# USBC_A.net
KiCad netlist of a schematic drawn in Altium Designer
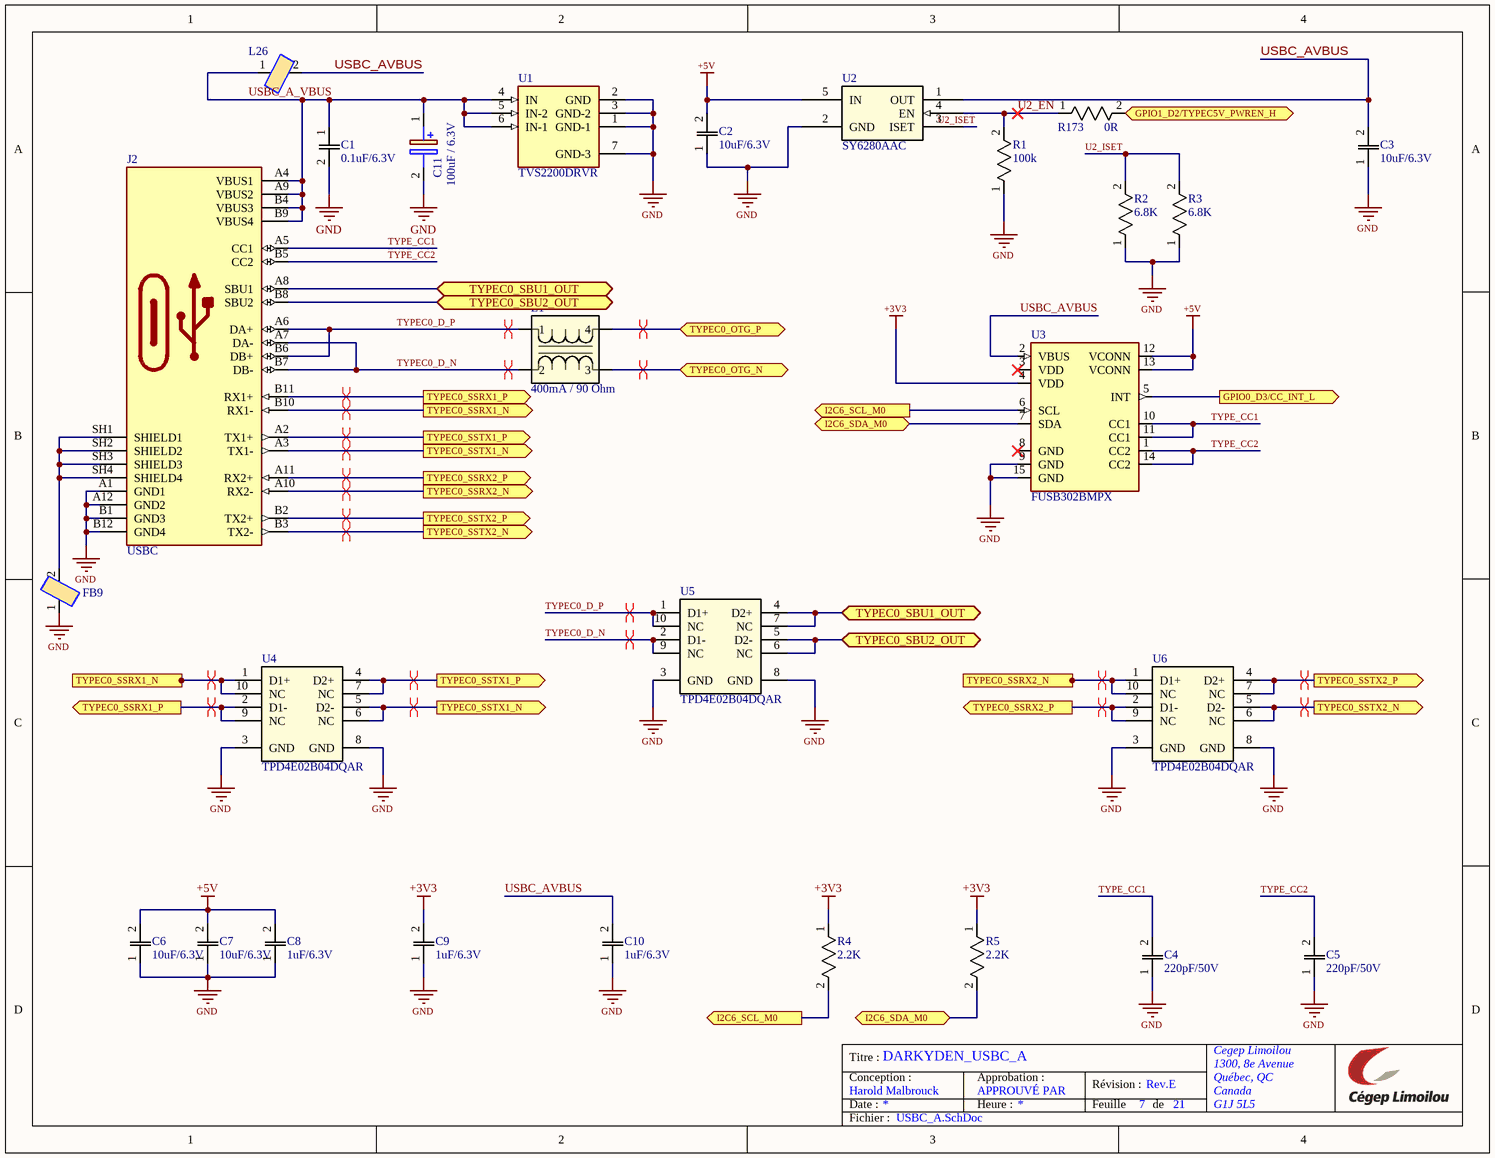
[diagram p0: USBC_A.SchDoc]

(export (version "E")
  (design (tool "Eeschema 10.0.6"))
  (components
    (comp (ref "C1")
      (value "0.1uF/6.3V")
      (footprint "C0805")
      (description "0.1uF 6.3V X7R 10% Pad SMD 0805 125C T/R")
      (fields
        (field (name "MOUSER PART NUMBER") "80-C0805C104K9R")
        (field (name "ARROW PART NUMBER") "C0805C104K9RACTU")
      )
      (libsource (lib "DARKYDEN") (part "C0805C104K9RACTU"))
    )
    (comp (ref "C2")
      (value "10uF/6.3V")
      (footprint "C0805")
      (fields
        (field (name "MOUSER PART NUMBER") "80-C0805C106K9R")
        (field (name "ARROW PART NUMBER") "C0805C106K9RACTU")
        (field (name "MANUFACTURER") "KEMET")
      )
      (libsource (lib "DARKYDEN") (part "C0805C106K9RACTU"))
    )
    (comp (ref "C3")
      (value "10uF/6.3V")
      (footprint "C0805")
      (fields
        (field (name "MOUSER PART NUMBER") "80-C0805C106K9R")
        (field (name "ARROW PART NUMBER") "C0805C106K9RACTU")
        (field (name "MANUFACTURER") "KEMET")
      )
      (libsource (lib "DARKYDEN") (part "C0805C106K9RACTU"))
    )
    (comp (ref "C4")
      (value "220pF/50V")
      (footprint "C0805")
      (description "Cap Ceramic 220pF 50V X7R 20% Pad SMD 0805 125C T/R")
      (fields
        (field (name "MANUFACTURER") "KEMET")
        (field (name "MANUFACTURER PART NUMBER") "C0805C221M5RACTU")
      )
      (libsource (lib "DARKYDEN") (part "C0805C221M5RACTU"))
    )
    (comp (ref "C5")
      (value "220pF/50V")
      (footprint "C0805")
      (description "Cap Ceramic 220pF 50V X7R 20% Pad SMD 0805 125C T/R")
      (fields
        (field (name "MANUFACTURER") "KEMET")
        (field (name "MANUFACTURER PART NUMBER") "C0805C221M5RACTU")
      )
      (libsource (lib "DARKYDEN") (part "C0805C221M5RACTU"))
    )
    (comp (ref "C6")
      (value "10uF/6.3V")
      (footprint "C0805")
      (fields
        (field (name "MOUSER PART NUMBER") "80-C0805C106K9R")
        (field (name "ARROW PART NUMBER") "C0805C106K9RACTU")
        (field (name "MANUFACTURER") "KEMET")
      )
      (libsource (lib "DARKYDEN") (part "C0805C106K9RACTU"))
    )
    (comp (ref "C7")
      (value "10uF/6.3V")
      (footprint "C0805")
      (fields
        (field (name "MOUSER PART NUMBER") "80-C0805C106K9R")
        (field (name "ARROW PART NUMBER") "C0805C106K9RACTU")
        (field (name "MANUFACTURER") "KEMET")
      )
      (libsource (lib "DARKYDEN") (part "C0805C106K9RACTU"))
    )
    (comp (ref "C8")
      (value "1uF/6.3V")
      (footprint "C0805")
      (description "1 uF, 6.3 V, ± 10%, X7R, 0805 [2012 Metric] Multilayer Ceramic Capacitor,")
      (fields
        (field (name "MOUSER PART NUMBER") "80-C0805C105K9R")
        (field (name "ARROW PART NUMBER") "C0805C105K9RACTU")
      )
      (libsource (lib "DARKYDEN") (part "C0805C105K9RACTU"))
    )
    (comp (ref "C9")
      (value "1uF/6.3V")
      (footprint "C0805")
      (description "1 uF, 6.3 V, ± 10%, X7R, 0805 [2012 Metric] Multilayer Ceramic Capacitor,")
      (fields
        (field (name "MOUSER PART NUMBER") "80-C0805C105K9R")
        (field (name "ARROW PART NUMBER") "C0805C105K9RACTU")
      )
      (libsource (lib "DARKYDEN") (part "C0805C105K9RACTU"))
    )
    (comp (ref "C10")
      (value "1uF/6.3V")
      (footprint "C0805")
      (description "1 uF, 6.3 V, ± 10%, X7R, 0805 [2012 Metric] Multilayer Ceramic Capacitor,")
      (fields
        (field (name "MOUSER PART NUMBER") "80-C0805C105K9R")
        (field (name "ARROW PART NUMBER") "C0805C105K9RACTU")
      )
      (libsource (lib "DARKYDEN") (part "C0805C105K9RACTU"))
    )
    (comp (ref "C11")
      (value "100uF / 6.3V")
      (footprint "SamacSys:EEE0GA101SR")
      (description "100uF 6.3V 20% Cap Aluminum Lytic  SMD 0.36 Ohm 240mA 2000h 105C Automotive T/R")
      (fields
        (field (name "MOUSER PART NUMBER") "667-EEE-FPJ101UAR")
        (field (name "ARROW PART NUMBER") "EEE-FPJ101UAR")
      )
      (libsource (lib "SamacSys") (part "EEE-FPJ101UAR"))
    )
    (comp (ref "FB9")
      (value "220R / 100MHz")
      (footprint "SamacSys:BLM18SP221SN1B")
      (description "Ferrite Beads Multi-Layer 220Ohm 25% 100MHz 2A 50mOhm DCR 0603 Paper T/R")
      (fields
        (field (name "MOUSER PART NUMBER") "81-BLM18EG221SN1D")
        (field (name "ARROW PART NUMBER") "BLM18EG221SN1D")
      )
      (libsource (lib "SamacSys") (part "BLM18EG221SN1D"))
    )
    (comp (ref "J2")
      (value "USBC")
      (footprint "USB_C")
      (fields (field (name "MF") "Molex") (field (name "MP") "2012670005"))
      (libsource (lib "DARKYDEN") (part "USBC"))
    )
    (comp (ref "L1")
      (value "400mA / 90 Ohm")
      (footprint "SamacSys:ACM20129002PT002")
      (description "Ferrite Beads Wirewound Common Mode Filter 90Ohm 100MHz 400mA 0805 T/R")
      (fields
        (field (name "MOUSER PART NUMBER") "810-ACM20129002PT002")
        (field (name "ARROW PART NUMBER") "ACM2012-900-2P-T002")
      )
      (libsource (lib "SamacSys") (part "ACM2012-900-2P-T002"))
    )
    (comp (ref "L26")
      (value "FBMJ2125HM210NT")
      (footprint "INDC2012X105N")
      (description "Ferrite Beads Power Chip 21Ohm 30% 100MHz 6A 0.004Ohm DCR 0805 Automotive T/R")
      (fields
        (field (name "MANUFACTURER") "Taiyo Yuden")
        (field (name "MOUSER PART NUMBER") "963-FBMJ2125HM210NT")
      )
      (libsource (lib "SamacSys") (part "FBMJ2125HM210NT"))
    )
    (comp (ref "R1")
      (value "100k")
      (footprint "SamacSys:RESC1608X55N")
      (description "100K Ohm 5%  Res Thick Film 0603 1/10W +/-200ppm/ßC Molded SMD Punched Carrier T/R")
      (fields
        (field (name "MOUSER PART NUMBER") "667-ERJ-3GEYJ104V")
        (field (name "ARROW PART NUMBER") "ERJ-3GEYJ104V")
      )
      (libsource (lib "DARKYDEN") (part "ERJ-3GEYJ104V"))
    )
    (comp (ref "R2")
      (value "6.8K")
      (footprint "SamacSys:RESC1608X55N")
      (description "6.8 kOhm, ± 5%, 100 mW, 0603 [1608 Metric], Thick Film, General Purpose")
      (fields (field (name "ARROW PART NUMBER") "ERJ-3GEYJ682V") (field (name "MANUFACTURER") "Panasonic"))
      (libsource (lib "DARKYDEN") (part "ERJ-3GEYJ682V"))
    )
    (comp (ref "R3")
      (value "6.8K")
      (footprint "SamacSys:RESC1608X55N")
      (description "6.8 kOhm, ± 5%, 100 mW, 0603 [1608 Metric], Thick Film, General Purpose")
      (fields (field (name "ARROW PART NUMBER") "ERJ-3GEYJ682V") (field (name "MANUFACTURER") "Panasonic"))
      (libsource (lib "DARKYDEN") (part "ERJ-3GEYJ682V"))
    )
    (comp (ref "R4")
      (value "2.2K")
      (footprint "SamacSys:RESC1608X55N")
      (description "2.2 kOhm, ï¿½ 5%, 100 mW, 0603 [1608 Metric], Thick Film, General Purpose")
      (fields
        (field (name "MOUSER PART NUMBER") "667-ERJ-3GEYJ222V")
        (field (name "ARROW PART NUMBER") "ERJ-3GEYJ222V")
      )
      (libsource (lib "DARKYDEN") (part "ERJ-3GEYJ222V"))
    )
    (comp (ref "R5")
      (value "2.2K")
      (footprint "SamacSys:RESC1608X55N")
      (description "2.2 kOhm, ï¿½ 5%, 100 mW, 0603 [1608 Metric], Thick Film, General Purpose")
      (fields
        (field (name "MOUSER PART NUMBER") "667-ERJ-3GEYJ222V")
        (field (name "ARROW PART NUMBER") "ERJ-3GEYJ222V")
      )
      (libsource (lib "DARKYDEN") (part "ERJ-3GEYJ222V"))
    )
    (comp (ref "R173")
      (value "0R")
      (footprint "RESC1608X55N")
      (description "Zero Ohm Resistor, Jumper, 0603 [1608 Metric], Thick Film, 100 mW, 1 A, Surface Mount")
      (fields
        (field (name "MOUSER PART NUMBER") "667-ERJ-3GEY0R00V")
        (field (name "ARROW PART NUMBER") "ERJ-3GEY0R00V")
      )
      (libsource (lib "DARKYDEN") (part "ERJ-3GEY0R00V"))
    )
    (comp (ref "U1")
      (value "TVS2200DRVR")
      (footprint "SON65P200X200X80-7N")
      (description "ESD Suppressors / TVS Diodes 22V flat-clamp surge protection device 6-WSON -40 to 125")
      (fields (field (name "MF") "Texas Instruments"))
      (libsource (lib "TVS2200") (part "TVS2200DRVR"))
    )
    (comp (ref "U2")
      (value "SY6280AAC")
      (footprint "SamacSys:SOT95P285X140-5N")
      (description "2.4V~5.5V 80mΩ Active High 1 High-side switch SOT-23-5 Power Distribution Switches ROHS")
      (libsource (lib "SamacSys") (part "SY6280AAC"))
    )
    (comp (ref "U3")
      (value "FUSB302BMPX")
      (footprint "SamacSys:QFN50P250X250X80-15N")
      (description "USB Controller USB 3.1 USB Interface 14-MLP (2.5x2.5)")
      (fields (field (name "MOUSER PART NUMBER") "512-FUSB302BMPX"))
      (libsource (lib "SamacSys") (part "FUSB302BMPX"))
    )
    (comp (ref "U4")
      (value "TPD4E02B04DQAR")
      (footprint "DQA0010A")
      (description "TVS DIODE 3.6V 8.8V 10USON / 4-Channel ESD Protection Diode for USB Type-C and HDMI 2.0")
      (fields (field (name "MANUFACTURER") "Texas Instruments"))
      (libsource (lib "TPD4E02B04DQAR") (part "TPD4E02B04DQAR"))
    )
    (comp (ref "U5")
      (value "TPD4E02B04DQAR")
      (footprint "DQA0010A")
      (description "TVS DIODE 3.6V 8.8V 10USON / 4-Channel ESD Protection Diode for USB Type-C and HDMI 2.0")
      (fields (field (name "MANUFACTURER") "Texas Instruments"))
      (libsource (lib "TPD4E02B04DQAR") (part "TPD4E02B04DQAR"))
    )
    (comp (ref "U6")
      (value "TPD4E02B04DQAR")
      (footprint "DQA0010A")
      (description "TVS DIODE 3.6V 8.8V 10USON / 4-Channel ESD Protection Diode for USB Type-C and HDMI 2.0")
      (fields (field (name "MANUFACTURER") "Texas Instruments"))
      (libsource (lib "TPD4E02B04DQAR") (part "TPD4E02B04DQAR"))
    )
  )
  (nets
    (net (code "1") (name "+3V3") (class "Default")
      (node (ref "C9") (pin "2") (pinfunction "2_2") (pintype "passive"))
      (node (ref "R4") (pin "1") (pinfunction "1_1") (pintype "passive"))
      (node (ref "R5") (pin "1") (pinfunction "1_1") (pintype "passive"))
      (node (ref "U3") (pin "4") (pinfunction "VDD_4") (pintype "power_in"))
    )
    (net (code "2") (name "+5V") (class "Default")
      (node (ref "C2") (pin "2") (pinfunction "2_2") (pintype "passive"))
      (node (ref "C6") (pin "2") (pinfunction "2_2") (pintype "passive"))
      (node (ref "C7") (pin "2") (pinfunction "2_2") (pintype "passive"))
      (node (ref "C8") (pin "2") (pinfunction "2_2") (pintype "passive"))
      (node (ref "U2") (pin "5") (pinfunction "IN_5") (pintype "power_in"))
      (node (ref "U3") (pin "12") (pinfunction "VCONN_12") (pintype "power_in"))
      (node (ref "U3") (pin "13") (pinfunction "VCONN_13") (pintype "power_in"))
    )
    (net (code "3") (name "/GPIO0_D3{slash}CC_INT_L") (class "Default")
      (node (ref "U3") (pin "5") (pinfunction "INT_5") (pintype "output"))
    )
    (net (code "4") (name "/GPIO1_D2{slash}TYPEC5V_PWREN_H") (class "Default")
      (node (ref "R173") (pin "2") (pinfunction "2_2") (pintype "passive"))
    )
    (net (code "5") (name "/I2C6_SCL_M0") (class "Default")
      (node (ref "R4") (pin "2") (pinfunction "2_2") (pintype "passive"))
      (node (ref "U3") (pin "6") (pinfunction "SCL_6") (pintype "input"))
    )
    (net (code "6") (name "/I2C6_SDA_M0") (class "Default")
      (node (ref "R5") (pin "2") (pinfunction "2_2") (pintype "passive"))
      (node (ref "U3") (pin "7") (pinfunction "SDA_7") (pintype "bidirectional"))
    )
    (net (code "7") (name "/TYPEC0_D_N") (class "Default")
      (node (ref "J2") (pin "A7") (pinfunction "DA-_A7") (pintype "bidirectional"))
      (node (ref "J2") (pin "B7") (pinfunction "DB-_B7") (pintype "bidirectional"))
      (node (ref "L1") (pin "2") (pinfunction "2_2") (pintype "passive"))
      (node (ref "U5") (pin "2") (pinfunction "D1-_2") (pintype "passive"))
      (node (ref "U5") (pin "9") (pinfunction "NC_9") (pintype "passive"))
    )
    (net (code "8") (name "/TYPEC0_D_P") (class "Default")
      (node (ref "J2") (pin "A6") (pinfunction "DA+_A6") (pintype "bidirectional"))
      (node (ref "J2") (pin "B6") (pinfunction "DB+_B6") (pintype "bidirectional"))
      (node (ref "L1") (pin "1") (pinfunction "1_1") (pintype "passive"))
      (node (ref "U5") (pin "1") (pinfunction "D1+_1") (pintype "passive"))
      (node (ref "U5") (pin "10") (pinfunction "NC_10") (pintype "passive"))
    )
    (net (code "9") (name "/TYPEC0_OTG_N") (class "Default")
      (node (ref "L1") (pin "3") (pinfunction "3_3") (pintype "passive"))
    )
    (net (code "10") (name "/TYPEC0_OTG_P") (class "Default")
      (node (ref "L1") (pin "4") (pinfunction "4_4") (pintype "passive"))
    )
    (net (code "11") (name "/TYPEC0_SBU1_OUT") (class "Default")
      (node (ref "J2") (pin "A8") (pinfunction "SBU1_A8") (pintype "bidirectional"))
      (node (ref "U5") (pin "4") (pinfunction "D2+_4") (pintype "passive"))
      (node (ref "U5") (pin "7") (pinfunction "NC_7") (pintype "passive"))
    )
    (net (code "12") (name "/TYPEC0_SBU2_OUT") (class "Default")
      (node (ref "J2") (pin "B8") (pinfunction "SBU2_B8") (pintype "bidirectional"))
      (node (ref "U5") (pin "5") (pinfunction "D2-_5") (pintype "passive"))
      (node (ref "U5") (pin "6") (pinfunction "NC_6") (pintype "passive"))
    )
    (net (code "13") (name "/TYPEC0_SSRX1_N") (class "Default")
      (node (ref "J2") (pin "B10") (pinfunction "RX1-_B10") (pintype "input"))
      (node (ref "U4") (pin "1") (pinfunction "D1+_1") (pintype "passive"))
      (node (ref "U4") (pin "10") (pinfunction "NC_10") (pintype "passive"))
    )
    (net (code "14") (name "/TYPEC0_SSRX1_P") (class "Default")
      (node (ref "J2") (pin "B11") (pinfunction "RX1+_B11") (pintype "input"))
      (node (ref "U4") (pin "2") (pinfunction "D1-_2") (pintype "passive"))
      (node (ref "U4") (pin "9") (pinfunction "NC_9") (pintype "passive"))
    )
    (net (code "15") (name "/TYPEC0_SSRX2_N") (class "Default")
      (node (ref "J2") (pin "A10") (pinfunction "RX2-_A10") (pintype "input"))
      (node (ref "U6") (pin "1") (pinfunction "D1+_1") (pintype "passive"))
      (node (ref "U6") (pin "10") (pinfunction "NC_10") (pintype "passive"))
    )
    (net (code "16") (name "/TYPEC0_SSRX2_P") (class "Default")
      (node (ref "J2") (pin "A11") (pinfunction "RX2+_A11") (pintype "input"))
      (node (ref "U6") (pin "2") (pinfunction "D1-_2") (pintype "passive"))
      (node (ref "U6") (pin "9") (pinfunction "NC_9") (pintype "passive"))
    )
    (net (code "17") (name "/TYPEC0_SSTX1_N") (class "Default")
      (node (ref "J2") (pin "A3") (pinfunction "TX1-_A3") (pintype "output"))
      (node (ref "U4") (pin "5") (pinfunction "D2-_5") (pintype "passive"))
      (node (ref "U4") (pin "6") (pinfunction "NC_6") (pintype "passive"))
    )
    (net (code "18") (name "/TYPEC0_SSTX1_P") (class "Default")
      (node (ref "J2") (pin "A2") (pinfunction "TX1+_A2") (pintype "output"))
      (node (ref "U4") (pin "4") (pinfunction "D2+_4") (pintype "passive"))
      (node (ref "U4") (pin "7") (pinfunction "NC_7") (pintype "passive"))
    )
    (net (code "19") (name "/TYPEC0_SSTX2_N") (class "Default")
      (node (ref "J2") (pin "B3") (pinfunction "TX2-_B3") (pintype "output"))
      (node (ref "U6") (pin "5") (pinfunction "D2-_5") (pintype "passive"))
      (node (ref "U6") (pin "6") (pinfunction "NC_6") (pintype "passive"))
    )
    (net (code "20") (name "/TYPEC0_SSTX2_P") (class "Default")
      (node (ref "J2") (pin "B2") (pinfunction "TX2+_B2") (pintype "output"))
      (node (ref "U6") (pin "4") (pinfunction "D2+_4") (pintype "passive"))
      (node (ref "U6") (pin "7") (pinfunction "NC_7") (pintype "passive"))
    )
    (net (code "21") (name "/TYPE_CC1") (class "Default")
      (node (ref "C4") (pin "2") (pinfunction "2_2") (pintype "passive"))
      (node (ref "J2") (pin "A5") (pinfunction "CC1_A5") (pintype "bidirectional"))
      (node (ref "U3") (pin "10") (pinfunction "CC1_10") (pintype "bidirectional"))
      (node (ref "U3") (pin "11") (pinfunction "CC1_11") (pintype "bidirectional"))
    )
    (net (code "22") (name "/TYPE_CC2") (class "Default")
      (node (ref "C5") (pin "2") (pinfunction "2_2") (pintype "passive"))
      (node (ref "J2") (pin "B5") (pinfunction "CC2_B5") (pintype "bidirectional"))
      (node (ref "U3") (pin "1") (pinfunction "CC2_1") (pintype "bidirectional"))
      (node (ref "U3") (pin "14") (pinfunction "CC2_14") (pintype "bidirectional"))
    )
    (net (code "24") (name "/U2_ISET") (class "Default")
      (node (ref "R2") (pin "2") (pinfunction "2_2") (pintype "passive"))
      (node (ref "R3") (pin "2") (pinfunction "2_2") (pintype "passive"))
      (node (ref "U2") (pin "3") (pinfunction "ISET_3") (pintype "passive"))
    )
    (net (code "25") (name "/USBC_AVBUS") (class "Default")
      (node (ref "C10") (pin "2") (pinfunction "2_2") (pintype "passive"))
      (node (ref "C3") (pin "2") (pinfunction "2_2") (pintype "passive"))
      (node (ref "L26") (pin "2") (pinfunction "2_2") (pintype "passive"))
      (node (ref "U2") (pin "1") (pinfunction "OUT_1") (pintype "power_in"))
      (node (ref "U3") (pin "2") (pinfunction "VBUS_2") (pintype "input"))
    )
    (net (code "26") (name "/USBC_A_VBUS") (class "Default")
      (node (ref "C1") (pin "1") (pinfunction "1_1") (pintype "passive"))
      (node (ref "C11") (pin "1") (pinfunction "+_1") (pintype "passive"))
      (node (ref "J2") (pin "A4") (pinfunction "VBUS1_A4") (pintype "power_in"))
      (node (ref "J2") (pin "A9") (pinfunction "VBUS2_A9") (pintype "power_in"))
      (node (ref "J2") (pin "B4") (pinfunction "VBUS3_B4") (pintype "power_in"))
      (node (ref "J2") (pin "B9") (pinfunction "VBUS4_B9") (pintype "power_in"))
      (node (ref "L26") (pin "1") (pinfunction "1_1") (pintype "passive"))
      (node (ref "U1") (pin "4") (pinfunction "IN_4") (pintype "input"))
      (node (ref "U1") (pin "5") (pinfunction "IN-2_5") (pintype "input"))
      (node (ref "U1") (pin "6") (pinfunction "IN-1_6") (pintype "input"))
    )
    (net (code "27") (name "GND") (class "Default")
      (node (ref "C1") (pin "2") (pinfunction "2_2") (pintype "passive"))
      (node (ref "C10") (pin "1") (pinfunction "1_1") (pintype "passive"))
      (node (ref "C11") (pin "2") (pinfunction "-_2") (pintype "passive"))
      (node (ref "C2") (pin "1") (pinfunction "1_1") (pintype "passive"))
      (node (ref "C3") (pin "1") (pinfunction "1_1") (pintype "passive"))
      (node (ref "C4") (pin "1") (pinfunction "1_1") (pintype "passive"))
      (node (ref "C5") (pin "1") (pinfunction "1_1") (pintype "passive"))
      (node (ref "C6") (pin "1") (pinfunction "1_1") (pintype "passive"))
      (node (ref "C7") (pin "1") (pinfunction "1_1") (pintype "passive"))
      (node (ref "C8") (pin "1") (pinfunction "1_1") (pintype "passive"))
      (node (ref "C9") (pin "1") (pinfunction "1_1") (pintype "passive"))
      (node (ref "FB9") (pin "1") (pinfunction "1_1") (pintype "passive"))
      (node (ref "J2") (pin "A1") (pinfunction "GND1_A1") (pintype "passive"))
      (node (ref "J2") (pin "A12") (pinfunction "GND2_A12") (pintype "passive"))
      (node (ref "J2") (pin "B1") (pinfunction "GND3_B1") (pintype "passive"))
      (node (ref "J2") (pin "B12") (pinfunction "GND4_B12") (pintype "passive"))
      (node (ref "R1") (pin "1") (pinfunction "1_1") (pintype "passive"))
      (node (ref "R2") (pin "1") (pinfunction "1_1") (pintype "passive"))
      (node (ref "R3") (pin "1") (pinfunction "1_1") (pintype "passive"))
      (node (ref "U1") (pin "1") (pinfunction "GND-1_1") (pintype "passive"))
      (node (ref "U1") (pin "2") (pinfunction "GND_2") (pintype "passive"))
      (node (ref "U1") (pin "3") (pinfunction "GND-2_3") (pintype "passive"))
      (node (ref "U1") (pin "7") (pinfunction "GND-3_7") (pintype "passive"))
      (node (ref "U2") (pin "2") (pinfunction "GND_2") (pintype "passive"))
      (node (ref "U3") (pin "15") (pinfunction "GND_15") (pintype "passive"))
      (node (ref "U3") (pin "9") (pinfunction "GND_9") (pintype "passive"))
      (node (ref "U4") (pin "3") (pinfunction "GND_3") (pintype "passive"))
      (node (ref "U4") (pin "8") (pinfunction "GND_8") (pintype "passive"))
      (node (ref "U5") (pin "3") (pinfunction "GND_3") (pintype "passive"))
      (node (ref "U5") (pin "8") (pinfunction "GND_8") (pintype "passive"))
      (node (ref "U6") (pin "3") (pinfunction "GND_3") (pintype "passive"))
      (node (ref "U6") (pin "8") (pinfunction "GND_8") (pintype "passive"))
    )
    (net (code "28") (name "Net-(J2-SHIELD1)") (class "Default")
      (node (ref "FB9") (pin "2") (pinfunction "2_2") (pintype "passive"))
      (node (ref "J2") (pin "SH1") (pinfunction "SHIELD1_SH1") (pintype "passive"))
      (node (ref "J2") (pin "SH2") (pinfunction "SHIELD2_SH2") (pintype "passive"))
      (node (ref "J2") (pin "SH3") (pinfunction "SHIELD3_SH3") (pintype "passive"))
      (node (ref "J2") (pin "SH4") (pinfunction "SHIELD4_SH4") (pintype "passive"))
    )
    (net (code "29") (name "Net-(U2-EN)") (class "Default")
      (node (ref "R1") (pin "2") (pinfunction "2_2") (pintype "passive"))
      (node (ref "R173") (pin "1") (pinfunction "1_1") (pintype "passive"))
      (node (ref "U2") (pin "4") (pinfunction "EN_4") (pintype "input"))
    )
    (net (code "30") (name "unconnected-(U3-GND-Pad8)") (class "Default")
      (node (ref "U3") (pin "8") (pinfunction "GND_8") (pintype "passive+no_connect"))
    )
    (net (code "31") (name "unconnected-(U3-VDD-Pad3)") (class "Default")
      (node (ref "U3") (pin "3") (pinfunction "VDD_3") (pintype "power_in+no_connect"))
    )
  )
)
